# pi1.net
KiCad netlist of a schematic drawn in EAGLE
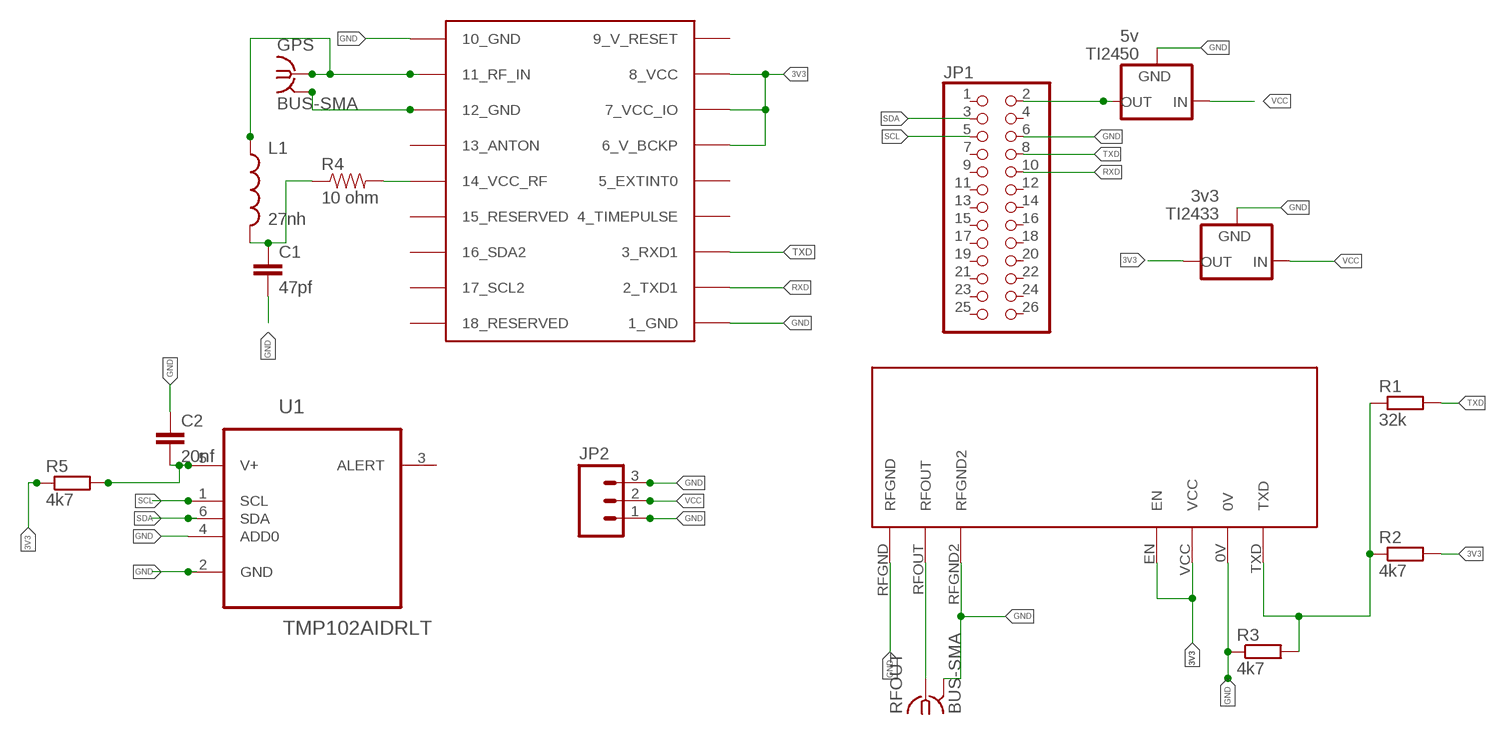
[diagram p0: schematic, sheet 1]

(export (version "E")
  (design (tool "Eeschema 10.0.6"))
  (components
    (comp (ref "C1")
      (value "47pf")
      (footprint "eagle-import:0603-CAP")
      (libsource (lib "eagle-import") (part "CAP0603-CAP"))
    )
    (comp (ref "C2")
      (value "20nf")
      (footprint "eagle-import:C0603")
      (libsource (lib "eagle-import") (part "C-EUC0603"))
    )
    (comp (ref "GPS")
      (value "BUS-SMA")
      (footprint "eagle-import:BUS-SMA")
      (libsource (lib "eagle-import") (part "BUS-SMA"))
    )
    (comp (ref "JP1")
      (value "PINHD-2X13")
      (footprint "eagle-import:2X13")
      (libsource (lib "eagle-import") (part "PINHD-2X13"))
    )
    (comp (ref "JP2")
      (value "M03PTH")
      (footprint "eagle-import:1X03")
      (libsource (lib "eagle-import") (part "M03PTH"))
    )
    (comp (ref "L1")
      (value "27nh")
      (footprint "eagle-import:0603")
      (libsource (lib "eagle-import") (part "INDUCTOR0603"))
    )
    (comp (ref "R1")
      (value "32k")
      (footprint "eagle-import:R0603")
      (libsource (lib "eagle-import") (part "R-EU_R0603"))
    )
    (comp (ref "R2")
      (value "4k7")
      (footprint "eagle-import:R0603")
      (libsource (lib "eagle-import") (part "R-EU_R0603"))
    )
    (comp (ref "R3")
      (value "4k7")
      (footprint "eagle-import:R0603")
      (libsource (lib "eagle-import") (part "R-EU_R0603"))
    )
    (comp (ref "R4")
      (value "10 ohm")
      (footprint "eagle-import:0603-RES")
      (libsource (lib "eagle-import") (part "RESISTOR0603"))
    )
    (comp (ref "R5")
      (value "4k7")
      (footprint "eagle-import:R0603")
      (libsource (lib "eagle-import") (part "R-EU_R0603"))
    )
    (comp (ref "RFOUT")
      (value "BUS-SMA")
      (footprint "eagle-import:BUS-SMA")
      (libsource (lib "eagle-import") (part "BUS-SMA"))
    )
    (comp (ref "TI2433")
      (value "3v3")
      (footprint "eagle-import:TO-220-ALT")
      (libsource (lib "eagle-import") (part "V_REG_78XX-TO-220"))
    )
    (comp (ref "TI2450")
      (value "5v")
      (footprint "eagle-import:TO-220-ALT")
      (libsource (lib "eagle-import") (part "V_REG_78XX-TO-220"))
    )
    (comp (ref "U$1")
      (value "NTX2")
      (footprint "eagle-import:NTX2")
      (libsource (lib "eagle-import") (part "NTX2"))
    )
    (comp (ref "U$2")
      (value "UBLOX_MAX")
      (footprint "eagle-import:UBLOX_MAX")
      (libsource (lib "eagle-import") (part "UBLOX_MAX"))
    )
    (comp (ref "U1")
      (value "TMP102AIDRLT")
      (footprint "eagle-import:SOT50P160X60-6N")
      (libsource (lib "eagle-import") (part "TMP102AIDRLT"))
    )
  )
  (nets
    (net (code "1") (name "/9_V_RESET") (class "Default")
      (node (ref "U$2") (pin "9_V_RESET") (pinfunction "9_V_RESET_9_V_RESET") (pintype "power_in"))
    )
    (net (code "2") (name "3V3") (class "Default")
      (node (ref "C2") (pin "2") (pinfunction "2_2") (pintype "passive"))
      (node (ref "R2") (pin "2") (pinfunction "2_2") (pintype "passive"))
      (node (ref "R5") (pin "1") (pinfunction "1_1") (pintype "passive"))
      (node (ref "R5") (pin "2") (pinfunction "2_2") (pintype "passive"))
      (node (ref "TI2433") (pin "OUT") (pinfunction "OUT_OUT") (pintype "output"))
      (node (ref "U$1") (pin "EN") (pinfunction "EN_EN") (pintype "bidirectional"))
      (node (ref "U$1") (pin "VCC") (pinfunction "VCC_VCC") (pintype "bidirectional"))
      (node (ref "U$2") (pin "6_V_BCKP") (pinfunction "6_V_BCKP_6_V_BCKP") (pintype "bidirectional"))
      (node (ref "U$2") (pin "7_VCC_IO") (pinfunction "7_VCC_IO_7_VCC_IO") (pintype "power_in"))
      (node (ref "U$2") (pin "8_VCC") (pinfunction "8_VCC_8_VCC") (pintype "power_in"))
      (node (ref "U1") (pin "5") (pinfunction "V+_5") (pintype "power_in"))
    )
    (net (code "3") (name "GND") (class "Default")
      (node (ref "C1") (pin "2") (pinfunction "2_2") (pintype "passive"))
      (node (ref "C2") (pin "1") (pinfunction "1_1") (pintype "passive"))
      (node (ref "GPS") (pin "2") (pinfunction "GND_2") (pintype "power_in"))
      (node (ref "GPS") (pin "3") (pinfunction "GND_3") (pintype "power_in"))
      (node (ref "GPS") (pin "4") (pinfunction "GND_4") (pintype "power_in"))
      (node (ref "GPS") (pin "5") (pinfunction "GND_5") (pintype "power_in"))
      (node (ref "JP1") (pin "6") (pinfunction "6_6") (pintype "passive"))
      (node (ref "JP2") (pin "1") (pinfunction "1_1") (pintype "passive"))
      (node (ref "JP2") (pin "3") (pinfunction "3_3") (pintype "passive"))
      (node (ref "R3") (pin "1") (pinfunction "1_1") (pintype "passive"))
      (node (ref "RFOUT") (pin "2") (pinfunction "GND_2") (pintype "power_in"))
      (node (ref "RFOUT") (pin "3") (pinfunction "GND_3") (pintype "power_in"))
      (node (ref "RFOUT") (pin "4") (pinfunction "GND_4") (pintype "power_in"))
      (node (ref "RFOUT") (pin "5") (pinfunction "GND_5") (pintype "power_in"))
      (node (ref "TI2433") (pin "GND") (pinfunction "GND_GND") (pintype "input"))
      (node (ref "TI2450") (pin "GND") (pinfunction "GND_GND") (pintype "input"))
      (node (ref "U$1") (pin "0V") (pinfunction "0V_0V") (pintype "bidirectional"))
      (node (ref "U$1") (pin "RFGND") (pinfunction "RFGND_RFGND") (pintype "bidirectional"))
      (node (ref "U$1") (pin "RFGND2") (pinfunction "RFGND2_RFGND2") (pintype "bidirectional"))
      (node (ref "U$2") (pin "10_GND") (pinfunction "10_GND_10_GND") (pintype "power_in"))
      (node (ref "U$2") (pin "12_GND") (pinfunction "12_GND_12_GND") (pintype "power_in"))
      (node (ref "U$2") (pin "1_GND") (pinfunction "1_GND_1_GND") (pintype "power_in"))
      (node (ref "U1") (pin "2") (pinfunction "GND_2") (pintype "passive"))
      (node (ref "U1") (pin "4") (pinfunction "ADD0_4") (pintype "input"))
    )
    (net (code "4") (name "Net-(C1-Pad1)") (class "Default")
      (node (ref "C1") (pin "1") (pinfunction "1_1") (pintype "passive"))
      (node (ref "L1") (pin "2") (pinfunction "2_2") (pintype "passive"))
      (node (ref "R4") (pin "1") (pinfunction "1_1") (pintype "passive"))
    )
    (net (code "5") (name "Net-(GPS-Pad1)") (class "Default")
      (node (ref "GPS") (pin "1") (pinfunction "1_1") (pintype "passive"))
      (node (ref "L1") (pin "1") (pinfunction "1_1") (pintype "passive"))
      (node (ref "U$2") (pin "11_RF_IN") (pinfunction "11_RF_IN_11_RF_IN") (pintype "bidirectional"))
    )
    (net (code "6") (name "Net-(JP1-Pad2)") (class "Default")
      (node (ref "JP1") (pin "2") (pinfunction "2_2") (pintype "passive"))
      (node (ref "TI2450") (pin "OUT") (pinfunction "OUT_OUT") (pintype "output"))
    )
    (net (code "7") (name "Net-(R1-Pad1)") (class "Default")
      (node (ref "R1") (pin "1") (pinfunction "1_1") (pintype "passive"))
      (node (ref "R2") (pin "1") (pinfunction "1_1") (pintype "passive"))
      (node (ref "R3") (pin "2") (pinfunction "2_2") (pintype "passive"))
      (node (ref "U$1") (pin "TXD") (pinfunction "TXD_TXD") (pintype "bidirectional"))
    )
    (net (code "8") (name "Net-(R4-Pad2)") (class "Default")
      (node (ref "R4") (pin "2") (pinfunction "2_2") (pintype "passive"))
      (node (ref "U$2") (pin "14_VCC_RF") (pinfunction "14_VCC_RF_14_VCC_RF") (pintype "bidirectional"))
    )
    (net (code "9") (name "Net-(RFOUT-Pad1)") (class "Default")
      (node (ref "RFOUT") (pin "1") (pinfunction "1_1") (pintype "passive"))
      (node (ref "U$1") (pin "RFOUT") (pinfunction "RFOUT_RFOUT") (pintype "bidirectional"))
    )
    (net (code "10") (name "RXD") (class "Default")
      (node (ref "JP1") (pin "10") (pinfunction "10_10") (pintype "passive"))
      (node (ref "U$2") (pin "2_TXD1") (pinfunction "2_TXD1_2_TXD1") (pintype "bidirectional"))
    )
    (net (code "11") (name "SCL") (class "Default")
      (node (ref "JP1") (pin "5") (pinfunction "5_5") (pintype "passive"))
      (node (ref "U1") (pin "1") (pinfunction "SCL_1") (pintype "bidirectional"))
    )
    (net (code "12") (name "SDA") (class "Default")
      (node (ref "JP1") (pin "3") (pinfunction "3_3") (pintype "passive"))
      (node (ref "U1") (pin "6") (pinfunction "SDA_6") (pintype "bidirectional"))
    )
    (net (code "13") (name "TXD") (class "Default")
      (node (ref "JP1") (pin "8") (pinfunction "8_8") (pintype "passive"))
      (node (ref "R1") (pin "2") (pinfunction "2_2") (pintype "passive"))
      (node (ref "U$2") (pin "3_RXD1") (pinfunction "3_RXD1_3_RXD1") (pintype "bidirectional"))
    )
    (net (code "14") (name "VCC") (class "Default")
      (node (ref "JP2") (pin "2") (pinfunction "2_2") (pintype "passive"))
      (node (ref "TI2433") (pin "IN") (pinfunction "IN_IN") (pintype "input"))
      (node (ref "TI2450") (pin "IN") (pinfunction "IN_IN") (pintype "input"))
    )
    (net (code "15") (name "unconnected-(JP1-Pad1)") (class "Default")
      (node (ref "JP1") (pin "1") (pinfunction "1_1") (pintype "passive"))
    )
    (net (code "16") (name "unconnected-(JP1-Pad4)") (class "Default")
      (node (ref "JP1") (pin "4") (pinfunction "4_4") (pintype "passive"))
    )
    (net (code "17") (name "unconnected-(JP1-Pad7)") (class "Default")
      (node (ref "JP1") (pin "7") (pinfunction "7_7") (pintype "passive"))
    )
    (net (code "18") (name "unconnected-(JP1-Pad9)") (class "Default")
      (node (ref "JP1") (pin "9") (pinfunction "9_9") (pintype "passive"))
    )
    (net (code "19") (name "unconnected-(JP1-Pad11)") (class "Default")
      (node (ref "JP1") (pin "11") (pinfunction "11_11") (pintype "passive"))
    )
    (net (code "20") (name "unconnected-(JP1-Pad12)") (class "Default")
      (node (ref "JP1") (pin "12") (pinfunction "12_12") (pintype "passive"))
    )
    (net (code "21") (name "unconnected-(JP1-Pad13)") (class "Default")
      (node (ref "JP1") (pin "13") (pinfunction "13_13") (pintype "passive"))
    )
    (net (code "22") (name "unconnected-(JP1-Pad14)") (class "Default")
      (node (ref "JP1") (pin "14") (pinfunction "14_14") (pintype "passive"))
    )
    (net (code "23") (name "unconnected-(JP1-Pad15)") (class "Default")
      (node (ref "JP1") (pin "15") (pinfunction "15_15") (pintype "passive"))
    )
    (net (code "24") (name "unconnected-(JP1-Pad16)") (class "Default")
      (node (ref "JP1") (pin "16") (pinfunction "16_16") (pintype "passive"))
    )
    (net (code "25") (name "unconnected-(JP1-Pad17)") (class "Default")
      (node (ref "JP1") (pin "17") (pinfunction "17_17") (pintype "passive"))
    )
    (net (code "26") (name "unconnected-(JP1-Pad18)") (class "Default")
      (node (ref "JP1") (pin "18") (pinfunction "18_18") (pintype "passive"))
    )
    (net (code "27") (name "unconnected-(JP1-Pad19)") (class "Default")
      (node (ref "JP1") (pin "19") (pinfunction "19_19") (pintype "passive"))
    )
    (net (code "28") (name "unconnected-(JP1-Pad20)") (class "Default")
      (node (ref "JP1") (pin "20") (pinfunction "20_20") (pintype "passive"))
    )
    (net (code "29") (name "unconnected-(JP1-Pad21)") (class "Default")
      (node (ref "JP1") (pin "21") (pinfunction "21_21") (pintype "passive"))
    )
    (net (code "30") (name "unconnected-(JP1-Pad22)") (class "Default")
      (node (ref "JP1") (pin "22") (pinfunction "22_22") (pintype "passive"))
    )
    (net (code "31") (name "unconnected-(JP1-Pad23)") (class "Default")
      (node (ref "JP1") (pin "23") (pinfunction "23_23") (pintype "passive"))
    )
    (net (code "32") (name "unconnected-(JP1-Pad24)") (class "Default")
      (node (ref "JP1") (pin "24") (pinfunction "24_24") (pintype "passive"))
    )
    (net (code "33") (name "unconnected-(JP1-Pad25)") (class "Default")
      (node (ref "JP1") (pin "25") (pinfunction "25_25") (pintype "passive"))
    )
    (net (code "34") (name "unconnected-(JP1-Pad26)") (class "Default")
      (node (ref "JP1") (pin "26") (pinfunction "26_26") (pintype "passive"))
    )
    (net (code "35") (name "unconnected-(U$2-Pad4_TIMEPULSE)") (class "Default")
      (node (ref "U$2") (pin "4_TIMEPULSE") (pinfunction "4_TIMEPULSE_4_TIMEPULSE") (pintype "bidirectional"))
    )
    (net (code "36") (name "unconnected-(U$2-Pad5_EXTINT0)") (class "Default")
      (node (ref "U$2") (pin "5_EXTINT0") (pinfunction "5_EXTINT0_5_EXTINT0") (pintype "bidirectional"))
    )
    (net (code "37") (name "unconnected-(U$2-Pad13_ANTON)") (class "Default")
      (node (ref "U$2") (pin "13_ANTON") (pinfunction "13_ANTON_13_ANTON") (pintype "bidirectional"))
    )
    (net (code "38") (name "unconnected-(U$2-Pad15_RESERVED)") (class "Default")
      (node (ref "U$2") (pin "15_RESERVED") (pinfunction "15_RESERVED_15_RESERVED") (pintype "bidirectional"))
    )
    (net (code "39") (name "unconnected-(U$2-Pad16_SDA2)") (class "Default")
      (node (ref "U$2") (pin "16_SDA2") (pinfunction "16_SDA2_16_SDA2") (pintype "bidirectional"))
    )
    (net (code "40") (name "unconnected-(U$2-Pad17_SCL2)") (class "Default")
      (node (ref "U$2") (pin "17_SCL2") (pinfunction "17_SCL2_17_SCL2") (pintype "bidirectional"))
    )
    (net (code "41") (name "unconnected-(U$2-Pad18_RESERVED)") (class "Default")
      (node (ref "U$2") (pin "18_RESERVED") (pinfunction "18_RESERVED_18_RESERVED") (pintype "bidirectional"))
    )
    (net (code "42") (name "unconnected-(U1-ALERT-Pad3)") (class "Default")
      (node (ref "U1") (pin "3") (pinfunction "ALERT_3") (pintype "output"))
    )
  )
)
